# Memory.net
KiCad netlist of a schematic drawn in Altium Designer
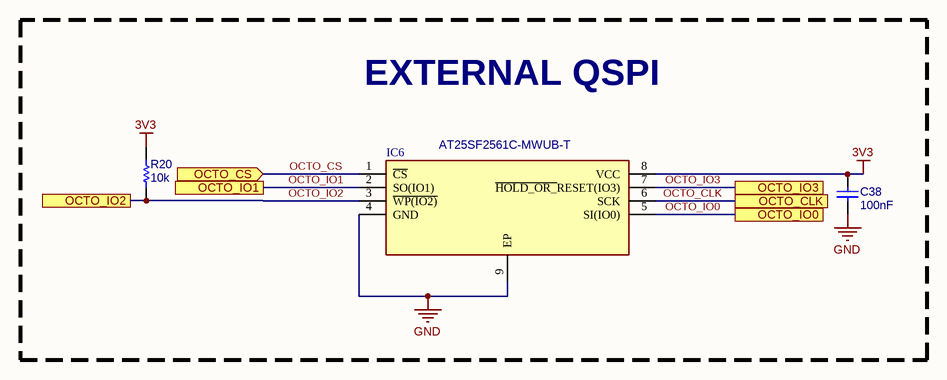
[diagram p0: Memory.SchDoc]

(export (version "E")
  (design (tool "Eeschema 10.0.6"))
  (components
    (comp (ref "C38")
      (value "100nF")
      (footprint "C0603")
      (description "Capacitor, MLCC, 100nF, 6V3, X5R, 10%, 0603, T=0,8mm")
      (fields
        (field (name "MANUFACTURER PART NUMBER") "CC0603KRX5R5BB104")
        (field (name "MANUFACTURER") "YAGEO")
        (field (name "PROVIDED_BY") "SUBCO")
      )
      (libsource (lib "Perth Aerospace Student Team") (part "CMP-035-000015-1"))
    )
    (comp (ref "IC6")
      (value "AT25SF2561C-MWUB-T")
      (footprint "C2Sv0.1:SON127P800X600X80-9N-D")
      (description "Integrated Circuit")
      (libsource (lib "*") (part "AT25SF2561C-MWUB-T"))
    )
    (comp (ref "R20")
      (value "10k")
      (footprint "RESC1608X55X25ML10T15-1")
      (description "Chip Resistor, 10k Ohm, 0.1 W, -55 to 155 degC, 0603 (1608 Metric)")
      (fields
        (field (name "POWER") "100mW")
        (field (name "TOLERANCE") "1%")
        (field (name "CREATED BY") "Micah Randall")
      )
      (libsource (lib "Perth Aerospace Student Team") (part "CMP-009-00006-5"))
    )
  )
  (nets
    (net (code "1") (name "/OCTO_CLK") (class "Default")
      (node (ref "IC6") (pin "6") (pinfunction "SCK_6") (pintype "passive"))
    )
    (net (code "2") (name "/OCTO_CS") (class "Default")
      (node (ref "IC6") (pin "1") (pinfunction "~{CS}_1") (pintype "passive"))
    )
    (net (code "3") (name "/OCTO_IO0") (class "Default")
      (node (ref "IC6") (pin "5") (pinfunction "SI(IO0)_5") (pintype "passive"))
    )
    (net (code "4") (name "/OCTO_IO1") (class "Default")
      (node (ref "IC6") (pin "2") (pinfunction "SO(IO1)_2") (pintype "passive"))
    )
    (net (code "5") (name "/OCTO_IO2") (class "Default")
      (node (ref "IC6") (pin "3") (pinfunction "~{WP(IO2)}_3") (pintype "passive"))
      (node (ref "R20") (pin "1") (pinfunction "1_1") (pintype "passive"))
    )
    (net (code "6") (name "/OCTO_IO3") (class "Default")
      (node (ref "IC6") (pin "7") (pinfunction "~{HOLD_OR_}RESET(IO3)_7") (pintype "passive"))
    )
    (net (code "7") (name "3V3") (class "Default")
      (node (ref "C38") (pin "1") (pinfunction "1_1") (pintype "passive"))
      (node (ref "IC6") (pin "8") (pinfunction "VCC_8") (pintype "passive"))
      (node (ref "R20") (pin "2") (pinfunction "2_2") (pintype "passive"))
    )
    (net (code "8") (name "GND") (class "Default")
      (node (ref "C38") (pin "2") (pinfunction "2_2") (pintype "passive"))
      (node (ref "IC6") (pin "4") (pinfunction "GND_4") (pintype "passive"))
      (node (ref "IC6") (pin "9") (pinfunction "EP_9") (pintype "passive"))
    )
  )
)
